# SB_TS_1_55.net
KiCad netlist of a schematic drawn in EAGLE
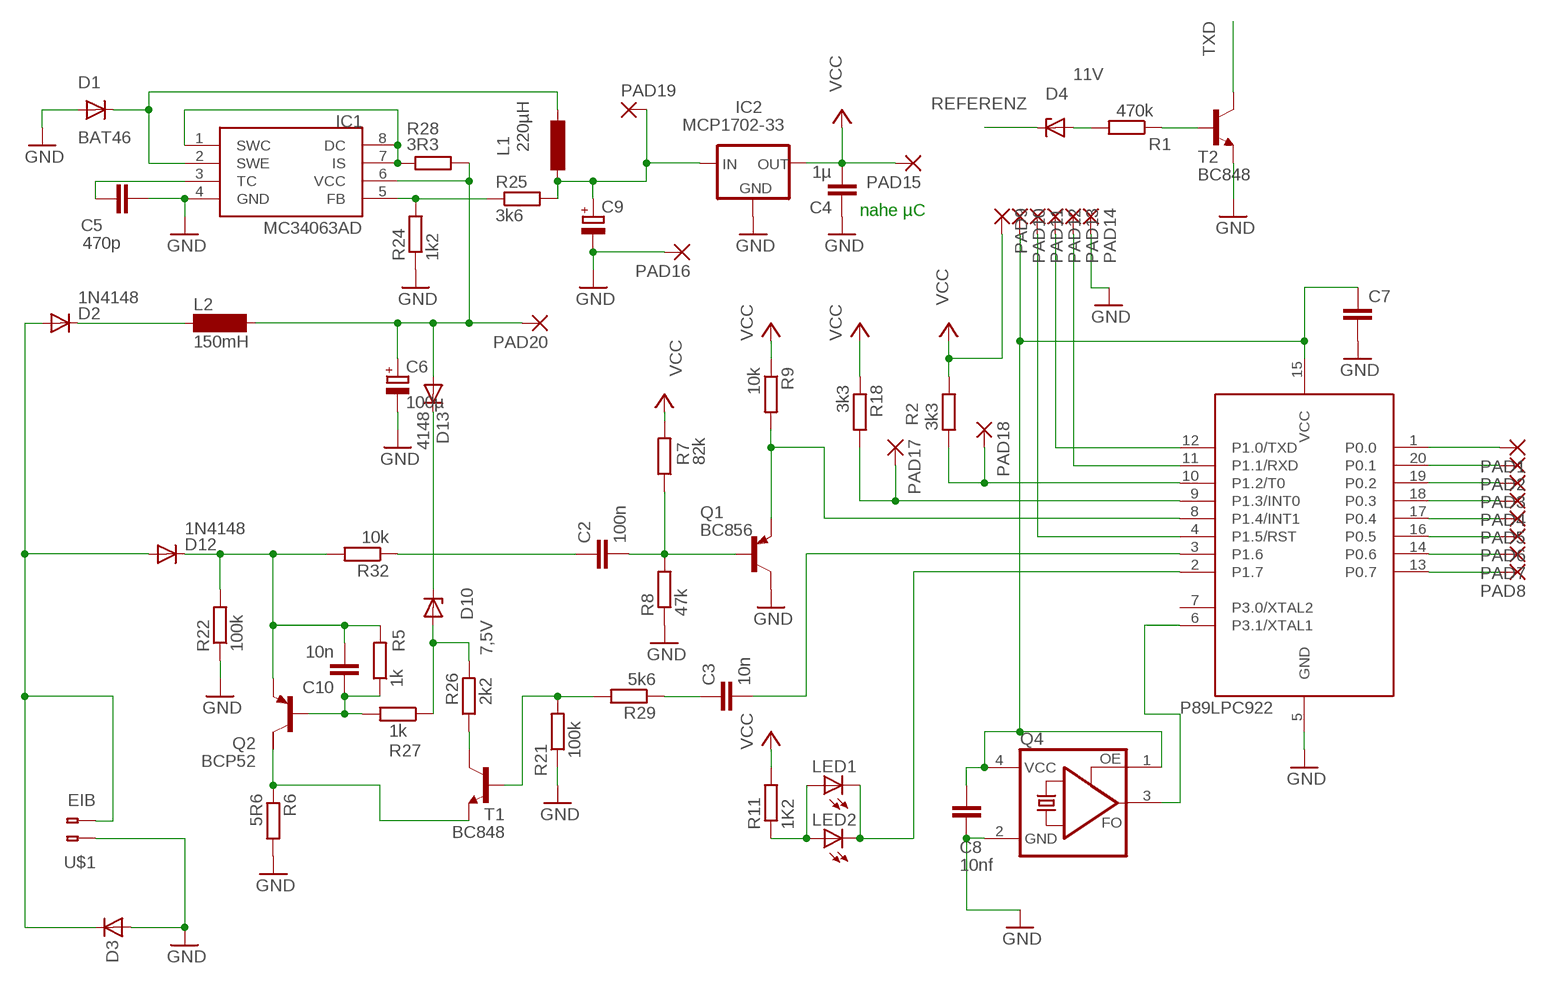
[diagram p0: schematic, sheet 1]

(export (version "E")
  (design (tool "Eeschema 10.0.6"))
  (components
    (comp (ref "C2")
      (value "100n")
      (footprint "eagle-import:C1206")
      (libsource (lib "eagle-import") (part "C-EUC1206"))
    )
    (comp (ref "C3")
      (value "10n")
      (footprint "eagle-import:C1206")
      (libsource (lib "eagle-import") (part "C-EUC1206"))
    )
    (comp (ref "C4")
      (value "1µ")
      (footprint "eagle-import:C1206")
      (libsource (lib "eagle-import") (part "C-EUC1206"))
    )
    (comp (ref "C5")
      (value "470p")
      (footprint "eagle-import:C1206")
      (libsource (lib "eagle-import") (part "C-EUC1206"))
    )
    (comp (ref "C6")
      (value "100µ")
      (footprint "eagle-import:SANYO-OSCON_SMD_C6")
      (libsource (lib "eagle-import") (part "CPOL-EUSANYO_SMD_C6"))
    )
    (comp (ref "C7")
      (value "C-EUC1206")
      (footprint "eagle-import:C1206")
      (libsource (lib "eagle-import") (part "C-EUC1206"))
    )
    (comp (ref "C8")
      (value "10nf")
      (footprint "eagle-import:C1206")
      (libsource (lib "eagle-import") (part "C-EUC1206"))
    )
    (comp (ref "C9")
      (value "CPOL-EUE2.5-5")
      (footprint "eagle-import:E2,5-5")
      (libsource (lib "eagle-import") (part "CPOL-EUE2.5-5"))
    )
    (comp (ref "C10")
      (value "10n")
      (footprint "eagle-import:C1206")
      (libsource (lib "eagle-import") (part "C-EUC1206"))
    )
    (comp (ref "D1")
      (value "BAT46")
      (footprint "eagle-import:MINIMELF")
      (libsource (lib "eagle-import") (part "DIODE-MINIMELF"))
    )
    (comp (ref "D2")
      (value "1N4148")
      (footprint "eagle-import:MINIMELF")
      (libsource (lib "eagle-import") (part "DIODE-MINIMELF"))
    )
    (comp (ref "D3")
      (value "SMAJ40AC")
      (footprint "eagle-import:SMB")
      (libsource (lib "eagle-import") (part "D-SMB"))
    )
    (comp (ref "D4")
      (value "11V")
      (footprint "eagle-import:MINIMELF")
      (libsource (lib "eagle-import") (part "ZPD"))
    )
    (comp (ref "D10")
      (value "7,5V")
      (footprint "eagle-import:MINIMELF")
      (libsource (lib "eagle-import") (part "ZPD"))
    )
    (comp (ref "D12")
      (value "1N4148")
      (footprint "eagle-import:MINIMELF")
      (libsource (lib "eagle-import") (part "DIODE-MINIMELF"))
    )
    (comp (ref "D13")
      (value "4148")
      (footprint "eagle-import:MINIMELF")
      (libsource (lib "eagle-import") (part "DIODE-MINIMELF"))
    )
    (comp (ref "IC1")
      (value "MC34063AD")
      (footprint "eagle-import:SOIC8")
      (libsource (lib "eagle-import") (part "MC34063AD"))
    )
    (comp (ref "IC2")
      (value "MCP1702-33")
      (footprint "eagle-import:79LXX")
      (libsource (lib "eagle-import") (part "79LXX"))
    )
    (comp (ref "L1")
      (value "220µH")
      (footprint "eagle-import:2200-11.43")
      (libsource (lib "eagle-import") (part "L-EU2200-11.43"))
    )
    (comp (ref "L2")
      (value "150mH")
      (footprint "eagle-import:SD12_1000")
      (libsource (lib "eagle-import") (part "SD12-1000"))
    )
    (comp (ref "LED1")
      (value "LEDCHIPLED_1206")
      (footprint "eagle-import:CHIPLED_1206")
      (libsource (lib "eagle-import") (part "LEDCHIPLED_1206"))
    )
    (comp (ref "LED2")
      (value "LED3MM")
      (footprint "eagle-import:LED3MM")
      (libsource (lib "eagle-import") (part "LED3MM"))
    )
    (comp (ref "PAD1")
      (value "SMD2")
      (footprint "eagle-import:SMD1,27-2,54")
      (libsource (lib "eagle-import") (part "SMD2"))
    )
    (comp (ref "PAD2")
      (value "SMD2")
      (footprint "eagle-import:SMD1,27-2,54")
      (libsource (lib "eagle-import") (part "SMD2"))
    )
    (comp (ref "PAD3")
      (value "SMD2")
      (footprint "eagle-import:SMD1,27-2,54")
      (libsource (lib "eagle-import") (part "SMD2"))
    )
    (comp (ref "PAD4")
      (value "SMD2")
      (footprint "eagle-import:SMD1,27-2,54")
      (libsource (lib "eagle-import") (part "SMD2"))
    )
    (comp (ref "PAD5")
      (value "SMD2")
      (footprint "eagle-import:SMD1,27-2,54")
      (libsource (lib "eagle-import") (part "SMD2"))
    )
    (comp (ref "PAD6")
      (value "SMD2")
      (footprint "eagle-import:SMD1,27-2,54")
      (libsource (lib "eagle-import") (part "SMD2"))
    )
    (comp (ref "PAD7")
      (value "SMD2")
      (footprint "eagle-import:SMD1,27-2,54")
      (libsource (lib "eagle-import") (part "SMD2"))
    )
    (comp (ref "PAD8")
      (value "SMD2")
      (footprint "eagle-import:SMD1,27-2,54")
      (libsource (lib "eagle-import") (part "SMD2"))
    )
    (comp (ref "PAD9")
      (value "SMD2")
      (footprint "eagle-import:SMD1,27-2,54")
      (libsource (lib "eagle-import") (part "SMD2"))
    )
    (comp (ref "PAD10")
      (value "SMD2")
      (footprint "eagle-import:SMD1,27-2,54")
      (libsource (lib "eagle-import") (part "SMD2"))
    )
    (comp (ref "PAD11")
      (value "SMD2")
      (footprint "eagle-import:SMD1,27-2,54")
      (libsource (lib "eagle-import") (part "SMD2"))
    )
    (comp (ref "PAD12")
      (value "SMD2")
      (footprint "eagle-import:SMD1,27-2,54")
      (libsource (lib "eagle-import") (part "SMD2"))
    )
    (comp (ref "PAD13")
      (value "SMD2")
      (footprint "eagle-import:SMD1,27-2,54")
      (libsource (lib "eagle-import") (part "SMD2"))
    )
    (comp (ref "PAD14")
      (value "SMD2")
      (footprint "eagle-import:SMD1,27-2,54")
      (libsource (lib "eagle-import") (part "SMD2"))
    )
    (comp (ref "PAD15")
      (value "SMD2")
      (footprint "eagle-import:SMD1,27-2,54")
      (libsource (lib "eagle-import") (part "SMD2"))
    )
    (comp (ref "PAD16")
      (value "SMD2")
      (footprint "eagle-import:SMD1,27-2,54")
      (libsource (lib "eagle-import") (part "SMD2"))
    )
    (comp (ref "PAD17")
      (value "SMD2")
      (footprint "eagle-import:SMD1,27-2,54")
      (libsource (lib "eagle-import") (part "SMD2"))
    )
    (comp (ref "PAD18")
      (value "SMD2")
      (footprint "eagle-import:SMD1,27-2,54")
      (libsource (lib "eagle-import") (part "SMD2"))
    )
    (comp (ref "PAD19")
      (value "SMD2")
      (footprint "eagle-import:SMD1,27-2,54")
      (libsource (lib "eagle-import") (part "SMD2"))
    )
    (comp (ref "PAD20")
      (value "SMD2")
      (footprint "eagle-import:SMD1,27-2,54")
      (libsource (lib "eagle-import") (part "SMD2"))
    )
    (comp (ref "Q1")
      (value "BC856")
      (footprint "eagle-import:SOT23-BEC")
      (libsource (lib "eagle-import") (part "BC856SMDALT1"))
    )
    (comp (ref "Q2")
      (value "BCP52")
      (footprint "eagle-import:SOT223")
      (libsource (lib "eagle-import") (part "FZT753SMD"))
    )
    (comp (ref "Q4")
      (value "ASFL")
      (footprint "eagle-import:ASF")
      (libsource (lib "eagle-import") (part "ASFL"))
    )
    (comp (ref "R1")
      (value "470k")
      (footprint "eagle-import:R1206")
      (libsource (lib "eagle-import") (part "R-EU_R1206"))
    )
    (comp (ref "R2")
      (value "3k3")
      (footprint "eagle-import:M1206")
      (libsource (lib "eagle-import") (part "R-EU_M1206"))
    )
    (comp (ref "R5")
      (value "1k")
      (footprint "eagle-import:R1206")
      (libsource (lib "eagle-import") (part "R-EU_R1206"))
    )
    (comp (ref "R6")
      (value "5R6")
      (footprint "eagle-import:R1206")
      (libsource (lib "eagle-import") (part "R-EU_R1206"))
    )
    (comp (ref "R7")
      (value "82k")
      (footprint "eagle-import:R1206")
      (libsource (lib "eagle-import") (part "R-EU_R1206"))
    )
    (comp (ref "R8")
      (value "47k")
      (footprint "eagle-import:M1206")
      (libsource (lib "eagle-import") (part "R-EU_M1206"))
    )
    (comp (ref "R9")
      (value "10k")
      (footprint "eagle-import:R1206")
      (libsource (lib "eagle-import") (part "R-EU_R1206"))
    )
    (comp (ref "R11")
      (value "1K2")
      (footprint "eagle-import:R1206")
      (libsource (lib "eagle-import") (part "R-EU_R1206"))
    )
    (comp (ref "R18")
      (value "3k3")
      (footprint "eagle-import:R1206")
      (libsource (lib "eagle-import") (part "R-EU_R1206"))
    )
    (comp (ref "R21")
      (value "100k")
      (footprint "eagle-import:R1206")
      (libsource (lib "eagle-import") (part "R-EU_R1206"))
    )
    (comp (ref "R22")
      (value "100k")
      (footprint "eagle-import:M1206")
      (libsource (lib "eagle-import") (part "R-EU_M1206"))
    )
    (comp (ref "R24")
      (value "1k2")
      (footprint "eagle-import:R1206")
      (libsource (lib "eagle-import") (part "R-EU_R1206"))
    )
    (comp (ref "R25")
      (value "3k6")
      (footprint "eagle-import:M1206")
      (libsource (lib "eagle-import") (part "R-EU_M1206"))
    )
    (comp (ref "R26")
      (value "2k2")
      (footprint "eagle-import:M1206")
      (libsource (lib "eagle-import") (part "R-EU_M1206"))
    )
    (comp (ref "R27")
      (value "1k")
      (footprint "eagle-import:R1206")
      (libsource (lib "eagle-import") (part "R-EU_R1206"))
    )
    (comp (ref "R28")
      (value "3R3")
      (footprint "eagle-import:M1206")
      (libsource (lib "eagle-import") (part "R-EU_M1206"))
    )
    (comp (ref "R29")
      (value "5k6")
      (footprint "eagle-import:R1206")
      (libsource (lib "eagle-import") (part "R-EU_R1206"))
    )
    (comp (ref "R32")
      (value "10k")
      (footprint "eagle-import:R1206")
      (libsource (lib "eagle-import") (part "R-EU_R1206"))
    )
    (comp (ref "T1")
      (value "BC848")
      (footprint "eagle-import:SOT23")
      (libsource (lib "eagle-import") (part "BC848"))
    )
    (comp (ref "T2")
      (value "BC848")
      (footprint "eagle-import:SOT23")
      (libsource (lib "eagle-import") (part "BC848"))
    )
    (comp (ref "U$1")
      (value "EIB")
      (footprint "eagle-import:BUSKLEMME243-724")
      (libsource (lib "eagle-import") (part "EIB"))
    )
    (comp (ref "U1")
      (value "89LPC922")
      (footprint "eagle-import:DIL20")
      (libsource (lib "eagle-import") (part "89LPC922"))
    )
  )
  (nets
    (net (code "1") (name "/REFERENZ") (class "Default")
      (node (ref "D10") (pin "A") (pinfunction "A_A") (pintype "passive"))
      (node (ref "D4") (pin "C") (pinfunction "C_C") (pintype "passive"))
      (node (ref "R26") (pin "2") (pinfunction "2_2") (pintype "passive"))
      (node (ref "R27") (pin "1") (pinfunction "1_1") (pintype "passive"))
    )
    (net (code "2") (name "/TXD") (class "Default")
      (node (ref "PAD12") (pin "1") (pinfunction "P_1") (pintype "passive"))
      (node (ref "T2") (pin "3") (pinfunction "C_3") (pintype "passive"))
      (node (ref "U1") (pin "12") (pinfunction "P1.0/TXD_12") (pintype "bidirectional"))
    )
    (net (code "3") (name "GND") (class "Default")
      (node (ref "C4") (pin "1") (pinfunction "1_1") (pintype "passive"))
      (node (ref "C5") (pin "2") (pinfunction "2_2") (pintype "passive"))
      (node (ref "C6") (pin "-") (pinfunction "-_-") (pintype "passive"))
      (node (ref "C7") (pin "2") (pinfunction "2_2") (pintype "passive"))
      (node (ref "C8") (pin "2") (pinfunction "2_2") (pintype "passive"))
      (node (ref "C9") (pin "-") (pinfunction "-_-") (pintype "passive"))
      (node (ref "D1") (pin "A") (pinfunction "A_A") (pintype "passive"))
      (node (ref "D3") (pin "2") (pinfunction "A_2") (pintype "passive"))
      (node (ref "IC1") (pin "4") (pinfunction "GND_4") (pintype "passive"))
      (node (ref "IC2") (pin "GND") (pinfunction "GND_GND") (pintype "input"))
      (node (ref "PAD14") (pin "1") (pinfunction "P_1") (pintype "passive"))
      (node (ref "PAD16") (pin "1") (pinfunction "P_1") (pintype "passive"))
      (node (ref "Q1") (pin "C") (pinfunction "C_C") (pintype "passive"))
      (node (ref "Q4") (pin "2") (pinfunction "GND_2") (pintype "power_in"))
      (node (ref "R21") (pin "1") (pinfunction "1_1") (pintype "passive"))
      (node (ref "R22") (pin "1") (pinfunction "1_1") (pintype "passive"))
      (node (ref "R24") (pin "1") (pinfunction "1_1") (pintype "passive"))
      (node (ref "R6") (pin "2") (pinfunction "2_2") (pintype "passive"))
      (node (ref "R8") (pin "1") (pinfunction "1_1") (pintype "passive"))
      (node (ref "T2") (pin "2") (pinfunction "E_2") (pintype "passive"))
      (node (ref "U$1") (pin "1") (pinfunction "B-1_1") (pintype "passive"))
      (node (ref "U1") (pin "5") (pinfunction "GND_5") (pintype "bidirectional"))
    )
    (net (code "4") (name "Net-(C2-Pad1)") (class "Default")
      (node (ref "C2") (pin "1") (pinfunction "1_1") (pintype "passive"))
      (node (ref "R32") (pin "1") (pinfunction "1_1") (pintype "passive"))
    )
    (net (code "5") (name "Net-(C2-Pad2)") (class "Default")
      (node (ref "C2") (pin "2") (pinfunction "2_2") (pintype "passive"))
      (node (ref "Q1") (pin "B") (pinfunction "B_B") (pintype "passive"))
      (node (ref "R7") (pin "1") (pinfunction "1_1") (pintype "passive"))
      (node (ref "R8") (pin "2") (pinfunction "2_2") (pintype "passive"))
    )
    (net (code "6") (name "Net-(C3-Pad1)") (class "Default")
      (node (ref "C3") (pin "1") (pinfunction "1_1") (pintype "passive"))
      (node (ref "R29") (pin "1") (pinfunction "1_1") (pintype "passive"))
    )
    (net (code "7") (name "Net-(D2-PadC)") (class "Default")
      (node (ref "D2") (pin "C") (pinfunction "C_C") (pintype "passive"))
      (node (ref "L2") (pin "1") (pinfunction "1_1") (pintype "passive"))
    )
    (net (code "8") (name "Net-(D3-C)") (class "Default")
      (node (ref "D12") (pin "A") (pinfunction "A_A") (pintype "passive"))
      (node (ref "D2") (pin "A") (pinfunction "A_A") (pintype "passive"))
      (node (ref "D3") (pin "1") (pinfunction "C_1") (pintype "passive"))
      (node (ref "U$1") (pin "2") (pinfunction "B-2_2") (pintype "passive"))
    )
    (net (code "9") (name "Net-(D4-PadA)") (class "Default")
      (node (ref "D4") (pin "A") (pinfunction "A_A") (pintype "passive"))
      (node (ref "R1") (pin "2") (pinfunction "2_2") (pintype "passive"))
    )
    (net (code "10") (name "Net-(D10-PadC)") (class "Default")
      (node (ref "D10") (pin "C") (pinfunction "C_C") (pintype "passive"))
      (node (ref "D13") (pin "C") (pinfunction "C_C") (pintype "passive"))
    )
    (net (code "11") (name "Net-(IC1-DC)") (class "Default")
      (node (ref "IC1") (pin "1") (pinfunction "SWC_1") (pintype "passive"))
      (node (ref "IC1") (pin "7") (pinfunction "IS_7") (pintype "passive"))
      (node (ref "IC1") (pin "8") (pinfunction "DC_8") (pintype "passive"))
      (node (ref "R28") (pin "1") (pinfunction "1_1") (pintype "passive"))
    )
    (net (code "12") (name "Net-(IC1-FB)") (class "Default")
      (node (ref "IC1") (pin "5") (pinfunction "FB_5") (pintype "passive"))
      (node (ref "R24") (pin "2") (pinfunction "2_2") (pintype "passive"))
      (node (ref "R25") (pin "1") (pinfunction "1_1") (pintype "passive"))
    )
    (net (code "13") (name "Net-(IC1-SWE)") (class "Default")
      (node (ref "D1") (pin "C") (pinfunction "C_C") (pintype "passive"))
      (node (ref "IC1") (pin "2") (pinfunction "SWE_2") (pintype "passive"))
      (node (ref "L1") (pin "2") (pinfunction "2_2") (pintype "passive"))
    )
    (net (code "14") (name "Net-(IC1-TC)") (class "Default")
      (node (ref "C5") (pin "1") (pinfunction "1_1") (pintype "passive"))
      (node (ref "IC1") (pin "3") (pinfunction "TC_3") (pintype "passive"))
    )
    (net (code "15") (name "Net-(IC1-VCC)") (class "Default")
      (node (ref "C6") (pin "+") (pinfunction "+_+") (pintype "passive"))
      (node (ref "D13") (pin "A") (pinfunction "A_A") (pintype "passive"))
      (node (ref "IC1") (pin "6") (pinfunction "VCC_6") (pintype "passive"))
      (node (ref "L2") (pin "2") (pinfunction "2_2") (pintype "passive"))
      (node (ref "PAD20") (pin "1") (pinfunction "P_1") (pintype "passive"))
      (node (ref "R28") (pin "2") (pinfunction "2_2") (pintype "passive"))
    )
    (net (code "16") (name "Net-(LED1-PadA)") (class "Default")
      (node (ref "LED1") (pin "A") (pinfunction "A_A") (pintype "passive"))
      (node (ref "LED2") (pin "A") (pinfunction "A_A") (pintype "passive"))
      (node (ref "R11") (pin "1") (pinfunction "1_1") (pintype "passive"))
    )
    (net (code "17") (name "Net-(LED2-C)") (class "Default")
      (node (ref "LED1") (pin "C") (pinfunction "C_C") (pintype "passive"))
      (node (ref "LED2") (pin "K") (pinfunction "C_K") (pintype "passive"))
      (node (ref "U1") (pin "2") (pinfunction "P1.7_2") (pintype "bidirectional"))
    )
    (net (code "18") (name "Net-(PAD1-P)") (class "Default")
      (node (ref "PAD1") (pin "1") (pinfunction "P_1") (pintype "passive"))
      (node (ref "U1") (pin "1") (pinfunction "P0.0_1") (pintype "bidirectional"))
    )
    (net (code "19") (name "Net-(PAD2-P)") (class "Default")
      (node (ref "PAD2") (pin "1") (pinfunction "P_1") (pintype "passive"))
      (node (ref "U1") (pin "20") (pinfunction "P0.1_20") (pintype "bidirectional"))
    )
    (net (code "20") (name "Net-(PAD3-P)") (class "Default")
      (node (ref "PAD3") (pin "1") (pinfunction "P_1") (pintype "passive"))
      (node (ref "U1") (pin "19") (pinfunction "P0.2_19") (pintype "bidirectional"))
    )
    (net (code "21") (name "Net-(PAD4-P)") (class "Default")
      (node (ref "PAD4") (pin "1") (pinfunction "P_1") (pintype "passive"))
      (node (ref "U1") (pin "18") (pinfunction "P0.3_18") (pintype "bidirectional"))
    )
    (net (code "22") (name "Net-(PAD5-P)") (class "Default")
      (node (ref "PAD5") (pin "1") (pinfunction "P_1") (pintype "passive"))
      (node (ref "U1") (pin "17") (pinfunction "P0.4_17") (pintype "bidirectional"))
    )
    (net (code "23") (name "Net-(PAD6-P)") (class "Default")
      (node (ref "PAD6") (pin "1") (pinfunction "P_1") (pintype "passive"))
      (node (ref "U1") (pin "16") (pinfunction "P0.5_16") (pintype "bidirectional"))
    )
    (net (code "24") (name "Net-(PAD7-P)") (class "Default")
      (node (ref "PAD7") (pin "1") (pinfunction "P_1") (pintype "passive"))
      (node (ref "U1") (pin "14") (pinfunction "P0.6_14") (pintype "bidirectional"))
    )
    (net (code "25") (name "Net-(PAD8-P)") (class "Default")
      (node (ref "PAD8") (pin "1") (pinfunction "P_1") (pintype "passive"))
      (node (ref "U1") (pin "13") (pinfunction "P0.7_13") (pintype "bidirectional"))
    )
    (net (code "26") (name "Net-(PAD10-P)") (class "Default")
      (node (ref "C7") (pin "1") (pinfunction "1_1") (pintype "passive"))
      (node (ref "C8") (pin "1") (pinfunction "1_1") (pintype "passive"))
      (node (ref "PAD10") (pin "1") (pinfunction "P_1") (pintype "passive"))
      (node (ref "Q4") (pin "1") (pinfunction "OE_1") (pintype "input"))
      (node (ref "Q4") (pin "4") (pinfunction "VCC_4") (pintype "power_in"))
      (node (ref "U1") (pin "15") (pinfunction "VCC_15") (pintype "bidirectional"))
    )
    (net (code "27") (name "Net-(PAD11-P)") (class "Default")
      (node (ref "PAD11") (pin "1") (pinfunction "P_1") (pintype "passive"))
      (node (ref "U1") (pin "4") (pinfunction "P1.5/RST_4") (pintype "bidirectional"))
    )
    (net (code "28") (name "Net-(PAD13-P)") (class "Default")
      (node (ref "PAD13") (pin "1") (pinfunction "P_1") (pintype "passive"))
      (node (ref "U1") (pin "11") (pinfunction "P1.1/RXD_11") (pintype "bidirectional"))
    )
    (net (code "29") (name "Net-(PAD17-P)") (class "Default")
      (node (ref "PAD17") (pin "1") (pinfunction "P_1") (pintype "passive"))
      (node (ref "R18") (pin "2") (pinfunction "2_2") (pintype "passive"))
      (node (ref "U1") (pin "9") (pinfunction "P1.3/INT0_9") (pintype "bidirectional"))
    )
    (net (code "30") (name "Net-(PAD18-P)") (class "Default")
      (node (ref "PAD18") (pin "1") (pinfunction "P_1") (pintype "passive"))
      (node (ref "R2") (pin "2") (pinfunction "2_2") (pintype "passive"))
      (node (ref "U1") (pin "10") (pinfunction "P1.2/T0_10") (pintype "bidirectional"))
    )
    (net (code "31") (name "Net-(PAD19-P)") (class "Default")
      (node (ref "C9") (pin "+") (pinfunction "+_+") (pintype "passive"))
      (node (ref "IC2") (pin "IN") (pinfunction "IN_IN") (pintype "input"))
      (node (ref "L1") (pin "1") (pinfunction "1_1") (pintype "passive"))
      (node (ref "PAD19") (pin "1") (pinfunction "P_1") (pintype "passive"))
      (node (ref "R25") (pin "2") (pinfunction "2_2") (pintype "passive"))
    )
    (net (code "32") (name "Net-(Q2-B)") (class "Default")
      (node (ref "C10") (pin "1") (pinfunction "1_1") (pintype "passive"))
      (node (ref "Q2") (pin "1") (pinfunction "B_1") (pintype "passive"))
      (node (ref "R27") (pin "2") (pinfunction "2_2") (pintype "passive"))
      (node (ref "R5") (pin "1") (pinfunction "1_1") (pintype "passive"))
    )
    (net (code "33") (name "Net-(Q2-C)") (class "Default")
      (node (ref "Q2") (pin "2") (pinfunction "C_2") (pintype "passive"))
      (node (ref "R6") (pin "1") (pinfunction "1_1") (pintype "passive"))
      (node (ref "T1") (pin "2") (pinfunction "E_2") (pintype "passive"))
    )
    (net (code "34") (name "Net-(Q2-E)") (class "Default")
      (node (ref "C10") (pin "2") (pinfunction "2_2") (pintype "passive"))
      (node (ref "D12") (pin "C") (pinfunction "C_C") (pintype "passive"))
      (node (ref "Q2") (pin "3") (pinfunction "E_3") (pintype "passive"))
      (node (ref "R22") (pin "2") (pinfunction "2_2") (pintype "passive"))
      (node (ref "R32") (pin "2") (pinfunction "2_2") (pintype "passive"))
      (node (ref "R5") (pin "2") (pinfunction "2_2") (pintype "passive"))
    )
    (net (code "35") (name "Net-(Q4-FO)") (class "Default")
      (node (ref "Q4") (pin "3") (pinfunction "FO_3") (pintype "output"))
      (node (ref "U1") (pin "6") (pinfunction "P3.1/XTAL1_6") (pintype "bidirectional"))
    )
    (net (code "36") (name "Net-(T1-B)") (class "Default")
      (node (ref "R21") (pin "2") (pinfunction "2_2") (pintype "passive"))
      (node (ref "R29") (pin "2") (pinfunction "2_2") (pintype "passive"))
      (node (ref "T1") (pin "1") (pinfunction "B_1") (pintype "passive"))
    )
    (net (code "37") (name "Net-(T1-C)") (class "Default")
      (node (ref "R26") (pin "1") (pinfunction "1_1") (pintype "passive"))
      (node (ref "T1") (pin "3") (pinfunction "C_3") (pintype "passive"))
    )
    (net (code "38") (name "Net-(T2-B)") (class "Default")
      (node (ref "R1") (pin "1") (pinfunction "1_1") (pintype "passive"))
      (node (ref "T2") (pin "1") (pinfunction "B_1") (pintype "passive"))
    )
    (net (code "39") (name "Net-(U1-P1.4{slash}INT1)") (class "Default")
      (node (ref "Q1") (pin "E") (pinfunction "E_E") (pintype "passive"))
      (node (ref "R9") (pin "2") (pinfunction "2_2") (pintype "passive"))
      (node (ref "U1") (pin "8") (pinfunction "P1.4/INT1_8") (pintype "bidirectional"))
    )
    (net (code "40") (name "Net-(U1-P1.6)") (class "Default")
      (node (ref "C3") (pin "2") (pinfunction "2_2") (pintype "passive"))
      (node (ref "U1") (pin "3") (pinfunction "P1.6_3") (pintype "bidirectional"))
    )
    (net (code "41") (name "VCC") (class "Default")
      (node (ref "C4") (pin "2") (pinfunction "2_2") (pintype "passive"))
      (node (ref "IC2") (pin "OUT") (pinfunction "OUT_OUT") (pintype "passive"))
      (node (ref "PAD15") (pin "1") (pinfunction "P_1") (pintype "passive"))
      (node (ref "PAD9") (pin "1") (pinfunction "P_1") (pintype "passive"))
      (node (ref "R11") (pin "2") (pinfunction "2_2") (pintype "passive"))
      (node (ref "R18") (pin "1") (pinfunction "1_1") (pintype "passive"))
      (node (ref "R2") (pin "1") (pinfunction "1_1") (pintype "passive"))
      (node (ref "R7") (pin "2") (pinfunction "2_2") (pintype "passive"))
      (node (ref "R9") (pin "1") (pinfunction "1_1") (pintype "passive"))
    )
    (net (code "42") (name "unconnected-(Q2-C{slash}-Pad4)") (class "Default")
      (node (ref "Q2") (pin "4") (pinfunction "C/_4") (pintype "passive"))
    )
    (net (code "43") (name "unconnected-(U1-P3.0{slash}XTAL2-Pad7)") (class "Default")
      (node (ref "U1") (pin "7") (pinfunction "P3.0/XTAL2_7") (pintype "bidirectional"))
    )
  )
)
